# 1Sheeld_Schematics_v1_0_1.net
KiCad netlist of a schematic drawn in EAGLE
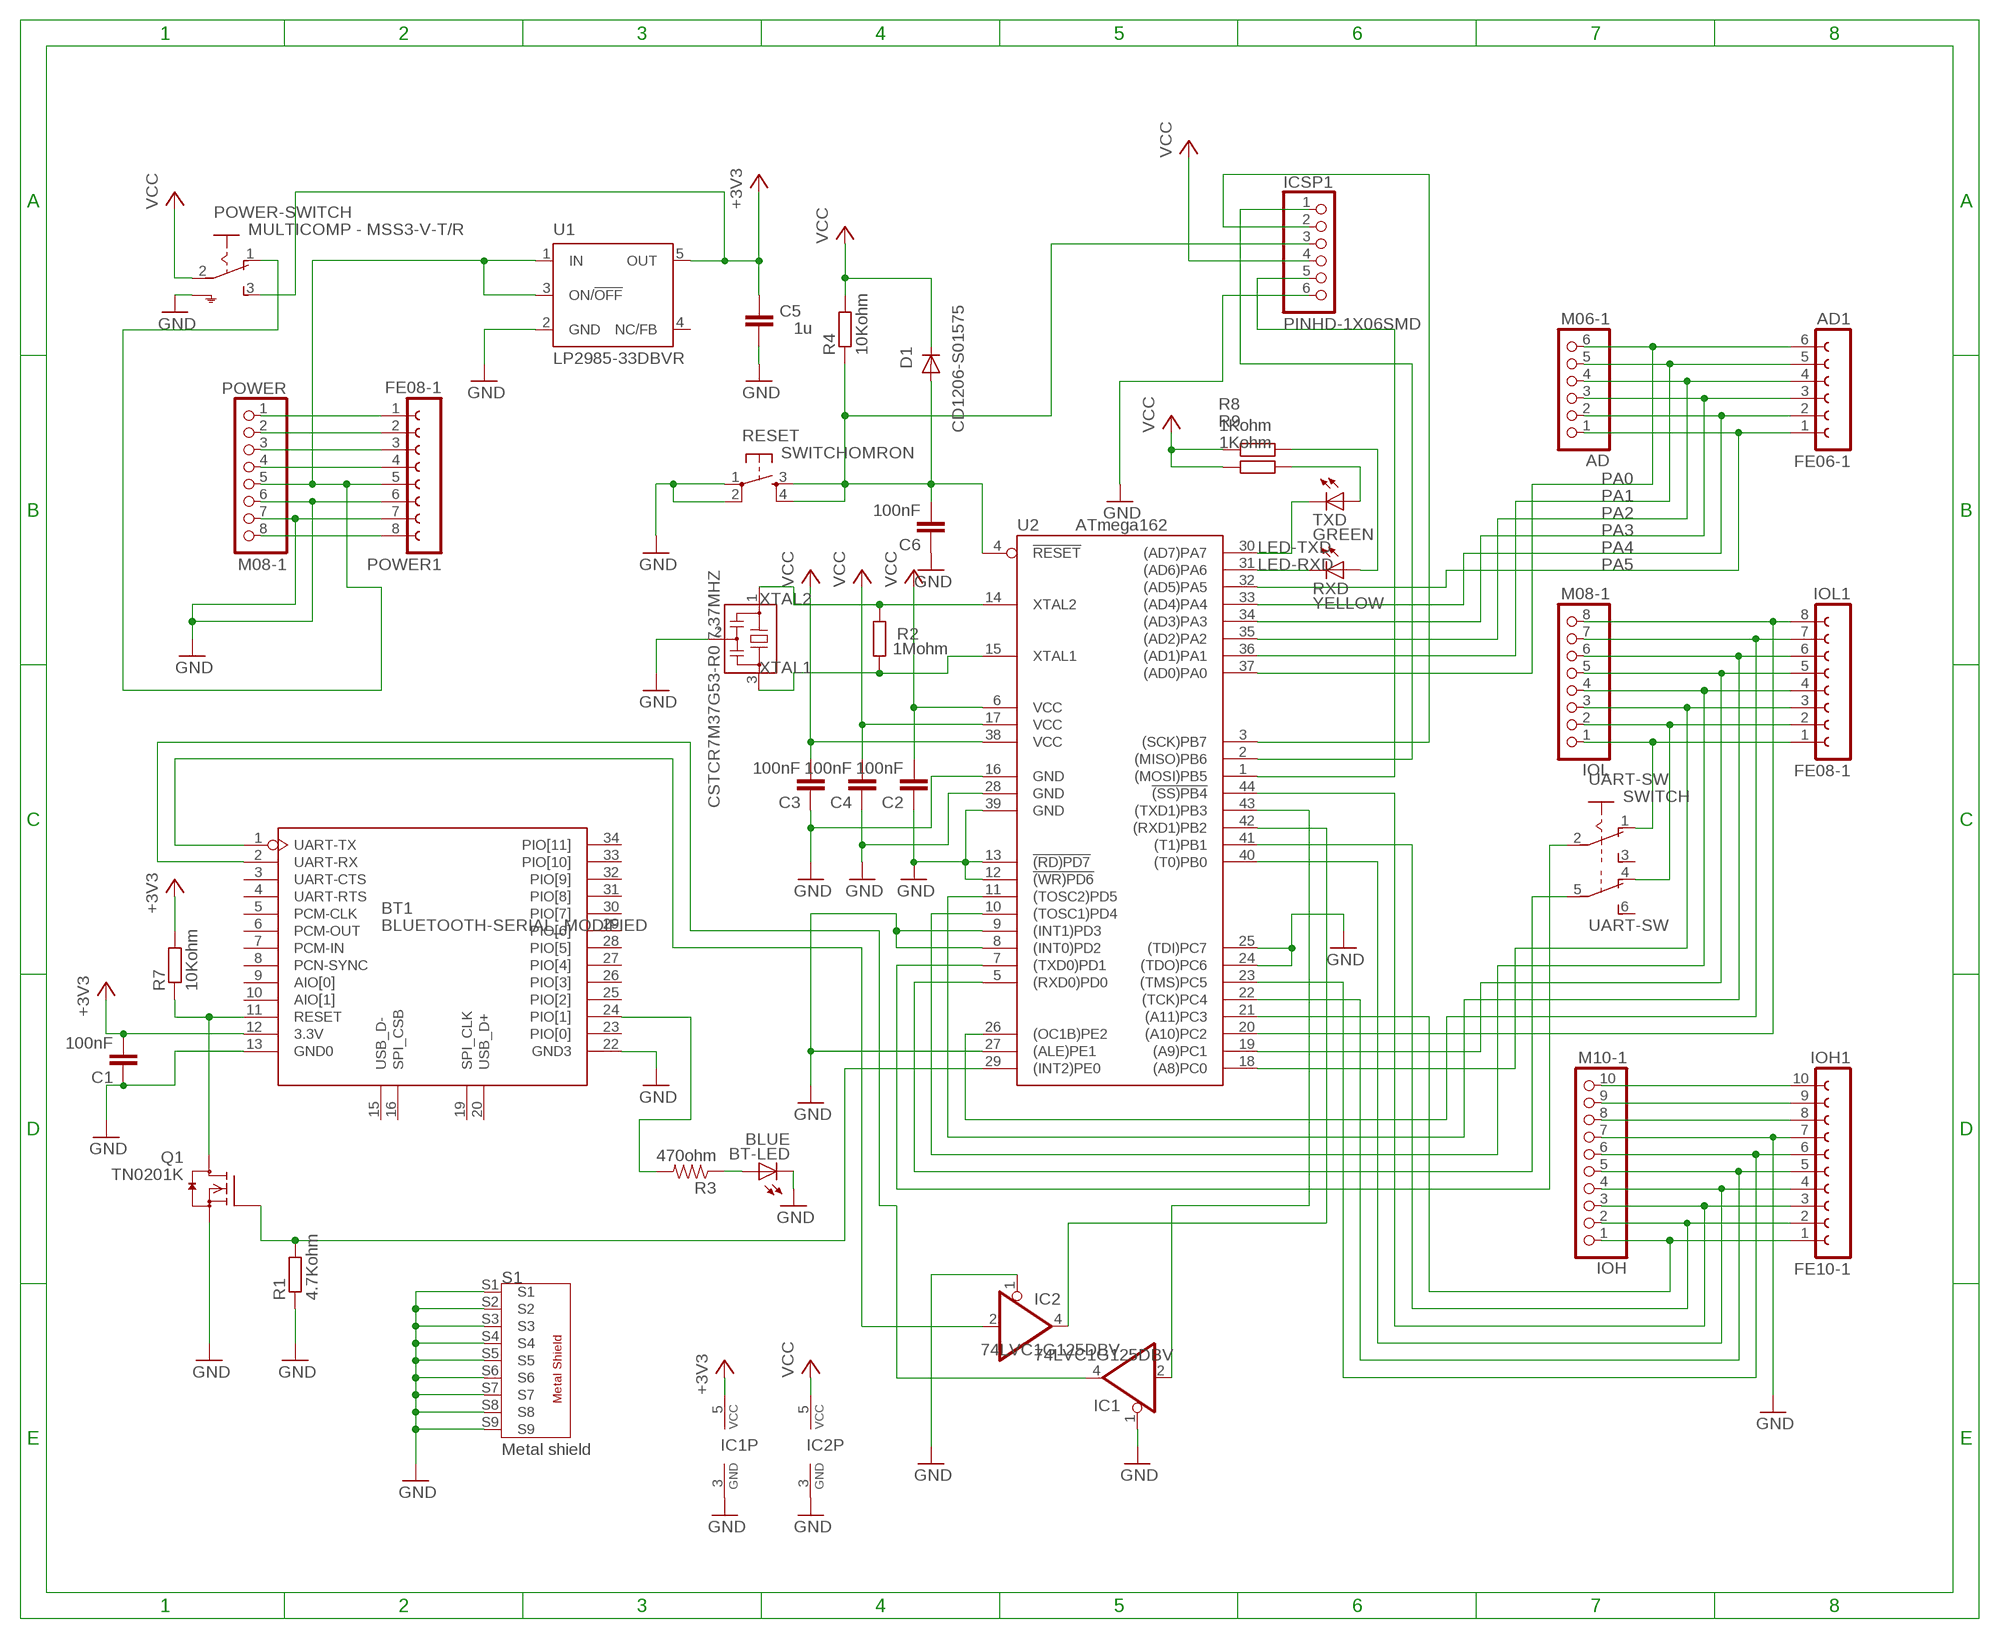
[diagram p0: schematic, sheet 1]

(export (version "E")
  (design (tool "Eeschema 10.0.6"))
  (components
    (comp (ref "AD")
      (value "M06-1")
      (footprint "eagle-import:1X06")
      (libsource (lib "eagle-import") (part "PINHD-1X6"))
    )
    (comp (ref "AD1")
      (value "FE06-1")
      (footprint "eagle-import:FE06")
      (libsource (lib "eagle-import") (part "FE06-1"))
    )
    (comp (ref "BT-LED")
      (value "BLUE")
      (footprint "eagle-import:CHIP-LED0805")
      (libsource (lib "eagle-import") (part "LEDCHIP-LED0805"))
    )
    (comp (ref "BT1")
      (value "BLUETOOTH-SERIAL_MODIFIED")
      (footprint "eagle-import:SERIAL_BLUETEETH_2")
      (libsource (lib "eagle-import") (part "BLUETOOTH-SERIAL_MODIFIED"))
    )
    (comp (ref "C1")
      (value "100nF")
      (footprint "eagle-import:C0603-ROUND")
      (libsource (lib "eagle-import") (part "C-EU0603-RND"))
    )
    (comp (ref "C2")
      (value "100nF")
      (footprint "eagle-import:C0603-ROUND")
      (libsource (lib "eagle-import") (part "C-EU0603-RND"))
    )
    (comp (ref "C3")
      (value "100nF")
      (footprint "eagle-import:C0603-ROUND")
      (libsource (lib "eagle-import") (part "C-EU0603-RND"))
    )
    (comp (ref "C4")
      (value "100nF")
      (footprint "eagle-import:C0603-ROUND")
      (libsource (lib "eagle-import") (part "C-EU0603-RND"))
    )
    (comp (ref "C5")
      (value "1u")
      (footprint "eagle-import:C0603-ROUND")
      (libsource (lib "eagle-import") (part "C-EU0603-RND"))
    )
    (comp (ref "C6")
      (value "100nF")
      (footprint "eagle-import:C0603-ROUND")
      (libsource (lib "eagle-import") (part "C-EU0603-RND"))
    )
    (comp (ref "D1")
      (value "CD1206-S01575")
      (footprint "eagle-import:MINIMELF")
      (libsource (lib "eagle-import") (part "DIODE-MINIMELF"))
    )
    (comp (ref "IC1")
      (value "74LVC1G125DBV")
      (footprint "eagle-import:SOT23-5")
      (libsource (lib "eagle-import") (part "741G125DBVLVC"))
    )
    (comp (ref "IC2")
      (value "74LVC1G125DBV")
      (footprint "eagle-import:SOT23-5")
      (libsource (lib "eagle-import") (part "741G125DBVLVC"))
    )
    (comp (ref "ICSP1")
      (value "PINHD-1X06SMD")
      (footprint "eagle-import:1X06_90SMD")
      (libsource (lib "eagle-import") (part "PINHD-1X06SMD"))
    )
    (comp (ref "IOH")
      (value "M10-1")
      (footprint "eagle-import:1X10")
      (libsource (lib "eagle-import") (part "PINHD-1X10_ARD"))
    )
    (comp (ref "IOH1")
      (value "FE10-1")
      (footprint "eagle-import:FE10")
      (libsource (lib "eagle-import") (part "FE10-1"))
    )
    (comp (ref "IOL")
      (value "M08-1")
      (footprint "eagle-import:1X08")
      (libsource (lib "eagle-import") (part "PINHD-1X8"))
    )
    (comp (ref "IOL1")
      (value "FE08-1")
      (footprint "eagle-import:FE08")
      (libsource (lib "eagle-import") (part "FE08-1"))
    )
    (comp (ref "POWER")
      (value "M08-1")
      (footprint "eagle-import:1X08")
      (libsource (lib "eagle-import") (part "PINHD-1X8"))
    )
    (comp (ref "POWER-SWITCH")
      (value "MULTICOMP - MSS3-V-T/R")
      (footprint "eagle-import:SWITCHMULTI")
      (libsource (lib "eagle-import") (part "SWITCHMULTI"))
    )
    (comp (ref "POWER1")
      (value "FE08-1")
      (footprint "eagle-import:FE08")
      (libsource (lib "eagle-import") (part "FE08-1"))
    )
    (comp (ref "Q1")
      (value "TN0201K")
      (footprint "eagle-import:SOT23")
      (libsource (lib "eagle-import") (part "TN0201K"))
    )
    (comp (ref "R1")
      (value "4.7Kohm")
      (footprint "eagle-import:M0805")
      (libsource (lib "eagle-import") (part "rcl_R-EU_M0805"))
    )
    (comp (ref "R2")
      (value "1Mohm")
      (footprint "eagle-import:R0603-ROUND")
      (libsource (lib "eagle-import") (part "R-EU_R0603"))
    )
    (comp (ref "R3")
      (value "470ohm")
      (footprint "eagle-import:0402-RES")
      (libsource (lib "eagle-import") (part "RESISTOR0402-RES"))
    )
    (comp (ref "R4")
      (value "10Kohm")
      (footprint "eagle-import:M0805")
      (libsource (lib "eagle-import") (part "rcl_R-EU_M0805"))
    )
    (comp (ref "R7")
      (value "10Kohm")
      (footprint "eagle-import:M0805")
      (libsource (lib "eagle-import") (part "rcl_R-EU_M0805"))
    )
    (comp (ref "R8")
      (value "1Kohm")
      (footprint "eagle-import:R0603-ROUND")
      (libsource (lib "eagle-import") (part "R-EU_R0603"))
    )
    (comp (ref "R9")
      (value "1Kohm")
      (footprint "eagle-import:R0603-ROUND")
      (libsource (lib "eagle-import") (part "R-EU_R0603"))
    )
    (comp (ref "RESET")
      (value "SWITCHOMRON")
      (footprint "eagle-import:OMRONSWITCH")
      (libsource (lib "eagle-import") (part "SWITCHOMRON"))
    )
    (comp (ref "RXD")
      (value "YELLOW")
      (footprint "eagle-import:CHIP-LED0805")
      (libsource (lib "eagle-import") (part "LEDCHIP-LED0805"))
    )
    (comp (ref "S1")
      (value "Metal shield")
      (footprint "eagle-import:BT_SHIELD")
      (libsource (lib "eagle-import") (part "EMI_SHIELD_BT"))
    )
    (comp (ref "TXD")
      (value "GREEN")
      (footprint "eagle-import:CHIP-LED0805")
      (libsource (lib "eagle-import") (part "LEDCHIP-LED0805"))
    )
    (comp (ref "U1")
      (value "LP2985-33DBVR")
      (footprint "eagle-import:SOT23-DBV")
      (libsource (lib "eagle-import") (part "LP2985-XXDBVR33"))
    )
    (comp (ref "U2")
      (value "ATmega162")
      (footprint "eagle-import:TQFP44")
      (libsource (lib "eagle-import") (part "ATMEGA162"))
    )
    (comp (ref "UART-SW")
      (value "SWITCH")
      (footprint "eagle-import:SWITCH")
      (libsource (lib "eagle-import") (part "SWITCH"))
    )
    (comp (ref "Y1")
      (value "CSTCR7M37G53-R0 7.37MHZ")
      (footprint "eagle-import:CSTCR6M")
      (fields (field (name "MPN") "CSTCR7M37G53-R0") (field (name "MPN_1") "CSTCR7M37G53-R0"))
      (libsource (lib "eagle-import") (part "CSTCR6M00G53Z"))
    )
  )
  (nets
    (net (code "1") (name "+3V3") (class "Default")
      (node (ref "BT1") (pin "12") (pinfunction "3.3V_12") (pintype "bidirectional"))
      (node (ref "C1") (pin "2") (pinfunction "2_2") (pintype "passive"))
      (node (ref "C5") (pin "2") (pinfunction "2_2") (pintype "passive"))
      (node (ref "IC1") (pin "5") (pinfunction "VCC_5") (pintype "power_in"))
      (node (ref "POWER-SWITCH") (pin "3") (pinfunction "S_3") (pintype "passive"))
      (node (ref "R7") (pin "2") (pinfunction "2_2") (pintype "passive"))
      (node (ref "U1") (pin "5") (pinfunction "OUT_5") (pintype "passive"))
    )
    (net (code "2") (name "/LED-RXD") (class "Default")
      (node (ref "RXD") (pin "C") (pinfunction "C_C") (pintype "passive"))
      (node (ref "U2") (pin "31") (pinfunction "(AD6)PA6_31") (pintype "bidirectional"))
    )
    (net (code "3") (name "/LED-TXD") (class "Default")
      (node (ref "TXD") (pin "C") (pinfunction "C_C") (pintype "passive"))
      (node (ref "U2") (pin "30") (pinfunction "(AD7)PA7_30") (pintype "bidirectional"))
    )
    (net (code "4") (name "/PA0") (class "Default")
      (node (ref "AD") (pin "6") (pinfunction "6_6") (pintype "passive"))
      (node (ref "AD1") (pin "6") (pinfunction "6_6") (pintype "passive"))
      (node (ref "U2") (pin "37") (pinfunction "(AD0)PA0_37") (pintype "bidirectional"))
    )
    (net (code "5") (name "/PA1") (class "Default")
      (node (ref "AD") (pin "5") (pinfunction "5_5") (pintype "passive"))
      (node (ref "AD1") (pin "5") (pinfunction "5_5") (pintype "passive"))
      (node (ref "U2") (pin "36") (pinfunction "(AD1)PA1_36") (pintype "bidirectional"))
    )
    (net (code "6") (name "/PA2") (class "Default")
      (node (ref "AD") (pin "4") (pinfunction "4_4") (pintype "passive"))
      (node (ref "AD1") (pin "4") (pinfunction "4_4") (pintype "passive"))
      (node (ref "U2") (pin "35") (pinfunction "(AD2)PA2_35") (pintype "bidirectional"))
    )
    (net (code "7") (name "/PA3") (class "Default")
      (node (ref "AD") (pin "3") (pinfunction "3_3") (pintype "passive"))
      (node (ref "AD1") (pin "3") (pinfunction "3_3") (pintype "passive"))
      (node (ref "U2") (pin "34") (pinfunction "(AD3)PA3_34") (pintype "bidirectional"))
    )
    (net (code "8") (name "/PA4") (class "Default")
      (node (ref "AD") (pin "2") (pinfunction "2_2") (pintype "passive"))
      (node (ref "AD1") (pin "2") (pinfunction "2_2") (pintype "passive"))
      (node (ref "U2") (pin "33") (pinfunction "(AD4)PA4_33") (pintype "bidirectional"))
    )
    (net (code "9") (name "/PA5") (class "Default")
      (node (ref "AD") (pin "1") (pinfunction "1_1") (pintype "passive"))
      (node (ref "AD1") (pin "1") (pinfunction "1_1") (pintype "passive"))
      (node (ref "U2") (pin "32") (pinfunction "(AD5)PA5_32") (pintype "bidirectional"))
    )
    (net (code "10") (name "/XTAL1") (class "Default")
      (node (ref "R2") (pin "1") (pinfunction "1_1") (pintype "passive"))
      (node (ref "U2") (pin "15") (pinfunction "XTAL1_15") (pintype "input"))
      (node (ref "Y1") (pin "3") (pinfunction "3_3") (pintype "passive"))
    )
    (net (code "11") (name "/XTAL2") (class "Default")
      (node (ref "R2") (pin "2") (pinfunction "2_2") (pintype "passive"))
      (node (ref "U2") (pin "14") (pinfunction "XTAL2_14") (pintype "input"))
      (node (ref "Y1") (pin "1") (pinfunction "1_1") (pintype "passive"))
    )
    (net (code "12") (name "GND") (class "Default")
      (node (ref "BT-LED") (pin "C") (pinfunction "C_C") (pintype "passive"))
      (node (ref "BT1") (pin "13") (pinfunction "GND0_13") (pintype "bidirectional"))
      (node (ref "BT1") (pin "22") (pinfunction "GND3_22") (pintype "bidirectional"))
      (node (ref "C1") (pin "1") (pinfunction "1_1") (pintype "passive"))
      (node (ref "C2") (pin "1") (pinfunction "1_1") (pintype "passive"))
      (node (ref "C3") (pin "1") (pinfunction "1_1") (pintype "passive"))
      (node (ref "C4") (pin "1") (pinfunction "1_1") (pintype "passive"))
      (node (ref "C5") (pin "1") (pinfunction "1_1") (pintype "passive"))
      (node (ref "C6") (pin "1") (pinfunction "1_1") (pintype "passive"))
      (node (ref "IC1") (pin "1") (pinfunction "OE_1") (pintype "input"))
      (node (ref "IC1") (pin "3") (pinfunction "GND_3") (pintype "power_in"))
      (node (ref "IC2") (pin "1") (pinfunction "OE_1") (pintype "input"))
      (node (ref "IC2") (pin "3") (pinfunction "GND_3") (pintype "power_in"))
      (node (ref "ICSP1") (pin "6") (pinfunction "6_6") (pintype "passive"))
      (node (ref "IOH") (pin "7") (pinfunction "7_7") (pintype "passive"))
      (node (ref "IOH1") (pin "7") (pinfunction "7_7") (pintype "passive"))
      (node (ref "POWER") (pin "6") (pinfunction "6_6") (pintype "passive"))
      (node (ref "POWER") (pin "7") (pinfunction "7_7") (pintype "passive"))
      (node (ref "POWER-SWITCH") (pin "P$4") (pinfunction "SH_P$4") (pintype "passive"))
      (node (ref "POWER-SWITCH") (pin "P$5") (pinfunction "SH_P$5") (pintype "passive"))
      (node (ref "POWER-SWITCH") (pin "P$6") (pinfunction "SH_P$6") (pintype "passive"))
      (node (ref "POWER-SWITCH") (pin "P$7") (pinfunction "SH_P$7") (pintype "passive"))
      (node (ref "POWER1") (pin "6") (pinfunction "6_6") (pintype "passive"))
      (node (ref "POWER1") (pin "7") (pinfunction "7_7") (pintype "passive"))
      (node (ref "Q1") (pin "2") (pinfunction "S_2") (pintype "passive"))
      (node (ref "R1") (pin "1") (pinfunction "1_1") (pintype "passive"))
      (node (ref "RESET") (pin "1") (pinfunction "P_1") (pintype "passive"))
      (node (ref "RESET") (pin "2") (pinfunction "P1_2") (pintype "passive"))
      (node (ref "S1") (pin "S1") (pinfunction "S1_S1") (pintype "bidirectional"))
      (node (ref "S1") (pin "S2") (pinfunction "S2_S2") (pintype "bidirectional"))
      (node (ref "S1") (pin "S3") (pinfunction "S3_S3") (pintype "bidirectional"))
      (node (ref "S1") (pin "S4") (pinfunction "S4_S4") (pintype "bidirectional"))
      (node (ref "S1") (pin "S5") (pinfunction "S5_S5") (pintype "bidirectional"))
      (node (ref "S1") (pin "S6") (pinfunction "S6_S6") (pintype "bidirectional"))
      (node (ref "S1") (pin "S7") (pinfunction "S7_S7") (pintype "bidirectional"))
      (node (ref "S1") (pin "S8") (pinfunction "S8_S8") (pintype "bidirectional"))
      (node (ref "S1") (pin "S9") (pinfunction "S9_S9") (pintype "bidirectional"))
      (node (ref "U1") (pin "2") (pinfunction "GND_2") (pintype "power_in"))
      (node (ref "U2") (pin "12") (pinfunction "~{(WR})PD6_12") (pintype "bidirectional"))
      (node (ref "U2") (pin "13") (pinfunction "~{(RD})PD7_13") (pintype "bidirectional"))
      (node (ref "U2") (pin "16") (pinfunction "GND_16") (pintype "power_in"))
      (node (ref "U2") (pin "24") (pinfunction "(TDO)PC6_24") (pintype "bidirectional"))
      (node (ref "U2") (pin "25") (pinfunction "(TDI)PC7_25") (pintype "bidirectional"))
      (node (ref "U2") (pin "27") (pinfunction "(ALE)PE1_27") (pintype "bidirectional"))
      (node (ref "U2") (pin "28") (pinfunction "GND_28") (pintype "power_in"))
      (node (ref "U2") (pin "39") (pinfunction "GND_39") (pintype "power_in"))
      (node (ref "U2") (pin "8") (pinfunction "(INT0)PD2_8") (pintype "bidirectional"))
      (node (ref "U2") (pin "9") (pinfunction "(INT1)PD3_9") (pintype "bidirectional"))
      (node (ref "Y1") (pin "2") (pinfunction "2_2") (pintype "passive"))
    )
    (net (code "13") (name "Net-(BT-LED-PadA)") (class "Default")
      (node (ref "BT-LED") (pin "A") (pinfunction "A_A") (pintype "passive"))
      (node (ref "R3") (pin "1") (pinfunction "1_1") (pintype "passive"))
    )
    (net (code "14") (name "Net-(BT1-PIO[1])") (class "Default")
      (node (ref "BT1") (pin "24") (pinfunction "PIO[1]_24") (pintype "bidirectional"))
      (node (ref "R3") (pin "2") (pinfunction "2_2") (pintype "passive"))
    )
    (net (code "15") (name "Net-(BT1-RESET)") (class "Default")
      (node (ref "BT1") (pin "11") (pinfunction "RESET_11") (pintype "bidirectional"))
      (node (ref "Q1") (pin "3") (pinfunction "D_3") (pintype "passive"))
      (node (ref "R7") (pin "1") (pinfunction "1_1") (pintype "passive"))
    )
    (net (code "16") (name "Net-(BT1-UART-RX)") (class "Default")
      (node (ref "BT1") (pin "2") (pinfunction "UART-RX_2") (pintype "bidirectional"))
      (node (ref "IC1") (pin "4") (pinfunction "O_4") (pintype "tri_state"))
    )
    (net (code "17") (name "Net-(BT1-UART-TX)") (class "Default")
      (node (ref "BT1") (pin "1") (pinfunction "UART-TX_1") (pintype "bidirectional"))
      (node (ref "IC2") (pin "2") (pinfunction "I_2") (pintype "input"))
    )
    (net (code "18") (name "Net-(IC1A-I)") (class "Default")
      (node (ref "IC1") (pin "2") (pinfunction "I_2") (pintype "input"))
      (node (ref "U2") (pin "43") (pinfunction "(TXD1)PB3_43") (pintype "bidirectional"))
    )
    (net (code "19") (name "Net-(IC2A-O)") (class "Default")
      (node (ref "IC2") (pin "4") (pinfunction "O_4") (pintype "tri_state"))
      (node (ref "U2") (pin "42") (pinfunction "(RXD1)PB2_42") (pintype "bidirectional"))
    )
    (net (code "20") (name "Net-(IOH-Pad8)") (class "Default")
      (node (ref "IOH") (pin "8") (pinfunction "8_8") (pintype "passive"))
      (node (ref "IOH1") (pin "8") (pinfunction "8_8") (pintype "passive"))
    )
    (net (code "21") (name "Net-(IOH-Pad9)") (class "Default")
      (node (ref "IOH") (pin "9") (pinfunction "9_9") (pintype "passive"))
      (node (ref "IOH1") (pin "9") (pinfunction "9_9") (pintype "passive"))
    )
    (net (code "22") (name "Net-(IOH-Pad10)") (class "Default")
      (node (ref "IOH") (pin "10") (pinfunction "10_10") (pintype "passive"))
      (node (ref "IOH1") (pin "10") (pinfunction "10_10") (pintype "passive"))
    )
    (net (code "23") (name "Net-(POWER-Pad1)") (class "Default")
      (node (ref "POWER") (pin "1") (pinfunction "1_1") (pintype "passive"))
      (node (ref "POWER1") (pin "1") (pinfunction "1_1") (pintype "passive"))
    )
    (net (code "24") (name "Net-(POWER-Pad2)") (class "Default")
      (node (ref "POWER") (pin "2") (pinfunction "2_2") (pintype "passive"))
      (node (ref "POWER1") (pin "2") (pinfunction "2_2") (pintype "passive"))
    )
    (net (code "25") (name "Net-(POWER-Pad3)") (class "Default")
      (node (ref "POWER") (pin "3") (pinfunction "3_3") (pintype "passive"))
      (node (ref "POWER1") (pin "3") (pinfunction "3_3") (pintype "passive"))
    )
    (net (code "26") (name "Net-(POWER-Pad4)") (class "Default")
      (node (ref "POWER") (pin "4") (pinfunction "4_4") (pintype "passive"))
      (node (ref "POWER1") (pin "4") (pinfunction "4_4") (pintype "passive"))
    )
    (net (code "27") (name "Net-(POWER-Pad8)") (class "Default")
      (node (ref "POWER") (pin "8") (pinfunction "8_8") (pintype "passive"))
      (node (ref "POWER1") (pin "8") (pinfunction "8_8") (pintype "passive"))
    )
    (net (code "28") (name "Net-(POWER-SWITCH-O)") (class "Default")
      (node (ref "POWER") (pin "5") (pinfunction "5_5") (pintype "passive"))
      (node (ref "POWER-SWITCH") (pin "1") (pinfunction "O_1") (pintype "passive"))
      (node (ref "POWER1") (pin "5") (pinfunction "5_5") (pintype "passive"))
      (node (ref "U1") (pin "1") (pinfunction "IN_1") (pintype "input"))
      (node (ref "U1") (pin "3") (pinfunction "ON/~{OFF}_3") (pintype "input"))
    )
    (net (code "29") (name "Net-(Q1-G)") (class "Default")
      (node (ref "Q1") (pin "1") (pinfunction "G_1") (pintype "passive"))
      (node (ref "R1") (pin "2") (pinfunction "2_2") (pintype "passive"))
      (node (ref "U2") (pin "29") (pinfunction "(INT2)PE0_29") (pintype "bidirectional"))
    )
    (net (code "30") (name "Net-(R8-Pad1)") (class "Default")
      (node (ref "R8") (pin "1") (pinfunction "1_1") (pintype "passive"))
      (node (ref "RXD") (pin "A") (pinfunction "A_A") (pintype "passive"))
    )
    (net (code "31") (name "Net-(R9-Pad1)") (class "Default")
      (node (ref "R9") (pin "1") (pinfunction "1_1") (pintype "passive"))
      (node (ref "TXD") (pin "A") (pinfunction "A_A") (pintype "passive"))
    )
    (net (code "32") (name "Net-(RESET-S)") (class "Default")
      (node (ref "C6") (pin "2") (pinfunction "2_2") (pintype "passive"))
      (node (ref "D1") (pin "A") (pinfunction "A_A") (pintype "passive"))
      (node (ref "ICSP1") (pin "3") (pinfunction "3_3") (pintype "passive"))
      (node (ref "R4") (pin "1") (pinfunction "1_1") (pintype "passive"))
      (node (ref "RESET") (pin "3") (pinfunction "S_3") (pintype "passive"))
      (node (ref "RESET") (pin "4") (pinfunction "S1_4") (pintype "passive"))
      (node (ref "U2") (pin "4") (pinfunction "~{RESET}_4") (pintype "input"))
    )
    (net (code "33") (name "Net-(U2-(A8)PC0)") (class "Default")
      (node (ref "IOL") (pin "3") (pinfunction "3_3") (pintype "passive"))
      (node (ref "IOL1") (pin "3") (pinfunction "3_3") (pintype "passive"))
      (node (ref "U2") (pin "18") (pinfunction "(A8)PC0_18") (pintype "bidirectional"))
    )
    (net (code "34") (name "Net-(U2-(A9)PC1)") (class "Default")
      (node (ref "IOL") (pin "5") (pinfunction "5_5") (pintype "passive"))
      (node (ref "IOL1") (pin "5") (pinfunction "5_5") (pintype "passive"))
      (node (ref "U2") (pin "19") (pinfunction "(A9)PC1_19") (pintype "bidirectional"))
    )
    (net (code "35") (name "Net-(U2-(A10)PC2)") (class "Default")
      (node (ref "IOL") (pin "8") (pinfunction "8_8") (pintype "passive"))
      (node (ref "IOL1") (pin "8") (pinfunction "8_8") (pintype "passive"))
      (node (ref "U2") (pin "20") (pinfunction "(A10)PC2_20") (pintype "bidirectional"))
    )
    (net (code "36") (name "Net-(U2-(A11)PC3)") (class "Default")
      (node (ref "IOH") (pin "1") (pinfunction "1_1") (pintype "passive"))
      (node (ref "IOH1") (pin "1") (pinfunction "1_1") (pintype "passive"))
      (node (ref "U2") (pin "21") (pinfunction "(A11)PC3_21") (pintype "bidirectional"))
    )
    (net (code "37") (name "Net-(U2-(MISO)PB6)") (class "Default")
      (node (ref "ICSP1") (pin "1") (pinfunction "1_1") (pintype "passive"))
      (node (ref "U2") (pin "2") (pinfunction "(MISO)PB6_2") (pintype "bidirectional"))
    )
    (net (code "38") (name "Net-(U2-(MOSI)PB5)") (class "Default")
      (node (ref "ICSP1") (pin "5") (pinfunction "5_5") (pintype "passive"))
      (node (ref "U2") (pin "1") (pinfunction "(MOSI)PB5_1") (pintype "bidirectional"))
    )
    (net (code "39") (name "Net-(U2-(OC1B)PE2)") (class "Default")
      (node (ref "IOL") (pin "7") (pinfunction "7_7") (pintype "passive"))
      (node (ref "IOL1") (pin "7") (pinfunction "7_7") (pintype "passive"))
      (node (ref "U2") (pin "26") (pinfunction "(OC1B)PE2_26") (pintype "bidirectional"))
    )
    (net (code "40") (name "Net-(U2-(RXD0)PD0)") (class "Default")
      (node (ref "U2") (pin "5") (pinfunction "(RXD0)PD0_5") (pintype "bidirectional"))
      (node (ref "UART-SW") (pin "5") (pinfunction "P_5") (pintype "passive"))
    )
    (net (code "41") (name "Net-(U2-(SCK)PB7)") (class "Default")
      (node (ref "ICSP1") (pin "2") (pinfunction "2_2") (pintype "passive"))
      (node (ref "U2") (pin "3") (pinfunction "(SCK)PB7_3") (pintype "bidirectional"))
    )
    (net (code "42") (name "Net-(U2-(T0)PB0)") (class "Default")
      (node (ref "IOH") (pin "4") (pinfunction "4_4") (pintype "passive"))
      (node (ref "IOH1") (pin "4") (pinfunction "4_4") (pintype "passive"))
      (node (ref "U2") (pin "40") (pinfunction "(T0)PB0_40") (pintype "bidirectional"))
    )
    (net (code "43") (name "Net-(U2-(T1)PB1)") (class "Default")
      (node (ref "IOH") (pin "2") (pinfunction "2_2") (pintype "passive"))
      (node (ref "IOH1") (pin "2") (pinfunction "2_2") (pintype "passive"))
      (node (ref "U2") (pin "41") (pinfunction "(T1)PB1_41") (pintype "bidirectional"))
    )
    (net (code "44") (name "Net-(U2-(TCK)PC4)") (class "Default")
      (node (ref "IOH") (pin "5") (pinfunction "5_5") (pintype "passive"))
      (node (ref "IOH1") (pin "5") (pinfunction "5_5") (pintype "passive"))
      (node (ref "U2") (pin "22") (pinfunction "(TCK)PC4_22") (pintype "bidirectional"))
    )
    (net (code "45") (name "Net-(U2-(TMS)PC5)") (class "Default")
      (node (ref "IOH") (pin "6") (pinfunction "6_6") (pintype "passive"))
      (node (ref "IOH1") (pin "6") (pinfunction "6_6") (pintype "passive"))
      (node (ref "U2") (pin "23") (pinfunction "(TMS)PC5_23") (pintype "bidirectional"))
    )
    (net (code "46") (name "Net-(U2-(TOSC1)PD4)") (class "Default")
      (node (ref "IOL") (pin "4") (pinfunction "4_4") (pintype "passive"))
      (node (ref "IOL1") (pin "4") (pinfunction "4_4") (pintype "passive"))
      (node (ref "U2") (pin "10") (pinfunction "(TOSC1)PD4_10") (pintype "bidirectional"))
    )
    (net (code "47") (name "Net-(U2-(TOSC2)PD5)") (class "Default")
      (node (ref "IOL") (pin "6") (pinfunction "6_6") (pintype "passive"))
      (node (ref "IOL1") (pin "6") (pinfunction "6_6") (pintype "passive"))
      (node (ref "U2") (pin "11") (pinfunction "(TOSC2)PD5_11") (pintype "bidirectional"))
    )
    (net (code "48") (name "Net-(U2-(TXD0)PD1)") (class "Default")
      (node (ref "U2") (pin "7") (pinfunction "(TXD0)PD1_7") (pintype "bidirectional"))
      (node (ref "UART-SW") (pin "2") (pinfunction "P_2") (pintype "passive"))
    )
    (net (code "49") (name "Net-(U2-~{(SS})PB4)") (class "Default")
      (node (ref "IOH") (pin "3") (pinfunction "3_3") (pintype "passive"))
      (node (ref "IOH1") (pin "3") (pinfunction "3_3") (pintype "passive"))
      (node (ref "U2") (pin "44") (pinfunction "~{(SS})PB4_44") (pintype "bidirectional"))
    )
    (net (code "50") (name "Net-(UART-SWA-O)") (class "Default")
      (node (ref "IOL") (pin "1") (pinfunction "1_1") (pintype "passive"))
      (node (ref "IOL1") (pin "1") (pinfunction "1_1") (pintype "passive"))
      (node (ref "UART-SW") (pin "1") (pinfunction "O_1") (pintype "passive"))
    )
    (net (code "51") (name "Net-(UART-SWB-O)") (class "Default")
      (node (ref "IOL") (pin "2") (pinfunction "2_2") (pintype "passive"))
      (node (ref "IOL1") (pin "2") (pinfunction "2_2") (pintype "passive"))
      (node (ref "UART-SW") (pin "4") (pinfunction "O_4") (pintype "passive"))
    )
    (net (code "52") (name "VCC") (class "Default")
      (node (ref "C2") (pin "2") (pinfunction "2_2") (pintype "passive"))
      (node (ref "C3") (pin "2") (pinfunction "2_2") (pintype "passive"))
      (node (ref "C4") (pin "2") (pinfunction "2_2") (pintype "passive"))
      (node (ref "D1") (pin "C") (pinfunction "C_C") (pintype "passive"))
      (node (ref "IC2") (pin "5") (pinfunction "VCC_5") (pintype "power_in"))
      (node (ref "ICSP1") (pin "4") (pinfunction "4_4") (pintype "passive"))
      (node (ref "POWER-SWITCH") (pin "2") (pinfunction "P_2") (pintype "passive"))
      (node (ref "R4") (pin "2") (pinfunction "2_2") (pintype "passive"))
      (node (ref "R8") (pin "2") (pinfunction "2_2") (pintype "passive"))
      (node (ref "R9") (pin "2") (pinfunction "2_2") (pintype "passive"))
      (node (ref "U2") (pin "17") (pinfunction "VCC_17") (pintype "power_in"))
      (node (ref "U2") (pin "38") (pinfunction "VCC_38") (pintype "power_in"))
      (node (ref "U2") (pin "6") (pinfunction "VCC_6") (pintype "power_in"))
    )
    (net (code "53") (name "unconnected-(BT1-AIO[0]-Pad9)") (class "Default")
      (node (ref "BT1") (pin "9") (pinfunction "AIO[0]_9") (pintype "bidirectional"))
    )
    (net (code "54") (name "unconnected-(BT1-AIO[1]-Pad10)") (class "Default")
      (node (ref "BT1") (pin "10") (pinfunction "AIO[1]_10") (pintype "bidirectional"))
    )
    (net (code "55") (name "unconnected-(BT1-PCM-CLK-Pad5)") (class "Default")
      (node (ref "BT1") (pin "5") (pinfunction "PCM-CLK_5") (pintype "bidirectional"))
    )
    (net (code "56") (name "unconnected-(BT1-PCM-IN-Pad7)") (class "Default")
      (node (ref "BT1") (pin "7") (pinfunction "PCM-IN_7") (pintype "bidirectional"))
    )
    (net (code "57") (name "unconnected-(BT1-PCM-OUT-Pad6)") (class "Default")
      (node (ref "BT1") (pin "6") (pinfunction "PCM-OUT_6") (pintype "bidirectional"))
    )
    (net (code "58") (name "unconnected-(BT1-PCN-SYNC-Pad8)") (class "Default")
      (node (ref "BT1") (pin "8") (pinfunction "PCN-SYNC_8") (pintype "bidirectional"))
    )
    (net (code "59") (name "unconnected-(BT1-PIO[0]-Pad23)") (class "Default")
      (node (ref "BT1") (pin "23") (pinfunction "PIO[0]_23") (pintype "bidirectional"))
    )
    (net (code "60") (name "unconnected-(BT1-PIO[2]-Pad25)") (class "Default")
      (node (ref "BT1") (pin "25") (pinfunction "PIO[2]_25") (pintype "bidirectional"))
    )
    (net (code "61") (name "unconnected-(BT1-PIO[3]-Pad26)") (class "Default")
      (node (ref "BT1") (pin "26") (pinfunction "PIO[3]_26") (pintype "bidirectional"))
    )
    (net (code "62") (name "unconnected-(BT1-PIO[4]-Pad27)") (class "Default")
      (node (ref "BT1") (pin "27") (pinfunction "PIO[4]_27") (pintype "bidirectional"))
    )
    (net (code "63") (name "unconnected-(BT1-PIO[5]-Pad28)") (class "Default")
      (node (ref "BT1") (pin "28") (pinfunction "PIO[5]_28") (pintype "bidirectional"))
    )
    (net (code "64") (name "unconnected-(BT1-PIO[6]-Pad29)") (class "Default")
      (node (ref "BT1") (pin "29") (pinfunction "PIO[6]_29") (pintype "bidirectional"))
    )
    (net (code "65") (name "unconnected-(BT1-PIO[7]-Pad30)") (class "Default")
      (node (ref "BT1") (pin "30") (pinfunction "PIO[7]_30") (pintype "bidirectional"))
    )
    (net (code "66") (name "unconnected-(BT1-PIO[8]-Pad31)") (class "Default")
      (node (ref "BT1") (pin "31") (pinfunction "PIO[8]_31") (pintype "bidirectional"))
    )
    (net (code "67") (name "unconnected-(BT1-PIO[9]-Pad32)") (class "Default")
      (node (ref "BT1") (pin "32") (pinfunction "PIO[9]_32") (pintype "bidirectional"))
    )
    (net (code "68") (name "unconnected-(BT1-PIO[10]-Pad33)") (class "Default")
      (node (ref "BT1") (pin "33") (pinfunction "PIO[10]_33") (pintype "bidirectional"))
    )
    (net (code "69") (name "unconnected-(BT1-PIO[11]-Pad34)") (class "Default")
      (node (ref "BT1") (pin "34") (pinfunction "PIO[11]_34") (pintype "bidirectional"))
    )
    (net (code "70") (name "unconnected-(BT1-SPI_CLK-Pad19)") (class "Default")
      (node (ref "BT1") (pin "19") (pinfunction "SPI_CLK_19") (pintype "bidirectional"))
    )
    (net (code "71") (name "unconnected-(BT1-SPI_CSB-Pad16)") (class "Default")
      (node (ref "BT1") (pin "16") (pinfunction "SPI_CSB_16") (pintype "bidirectional"))
    )
    (net (code "72") (name "unconnected-(BT1-UART-CTS-Pad3)") (class "Default")
      (node (ref "BT1") (pin "3") (pinfunction "UART-CTS_3") (pintype "bidirectional"))
    )
    (net (code "73") (name "unconnected-(BT1-UART-RTS-Pad4)") (class "Default")
      (node (ref "BT1") (pin "4") (pinfunction "UART-RTS_4") (pintype "bidirectional"))
    )
    (net (code "74") (name "unconnected-(BT1-USB_D+-Pad20)") (class "Default")
      (node (ref "BT1") (pin "20") (pinfunction "USB_D+_20") (pintype "bidirectional"))
    )
    (net (code "75") (name "unconnected-(BT1-USB_D--Pad15)") (class "Default")
      (node (ref "BT1") (pin "15") (pinfunction "USB_D-_15") (pintype "bidirectional"))
    )
    (net (code "76") (name "unconnected-(U1-NC{slash}FB-Pad4)") (class "Default")
      (node (ref "U1") (pin "4") (pinfunction "NC/FB_4") (pintype "passive"))
    )
    (net (code "77") (name "unconnected-(UART-SWA-S-Pad3)") (class "Default")
      (node (ref "UART-SW") (pin "3") (pinfunction "S_3") (pintype "passive"))
    )
    (net (code "78") (name "unconnected-(UART-SWB-S-Pad6)") (class "Default")
      (node (ref "UART-SW") (pin "6") (pinfunction "S_6") (pintype "passive"))
    )
  )
)
